# RX_DP.net
KiCad netlist of a schematic drawn in Altium Designer
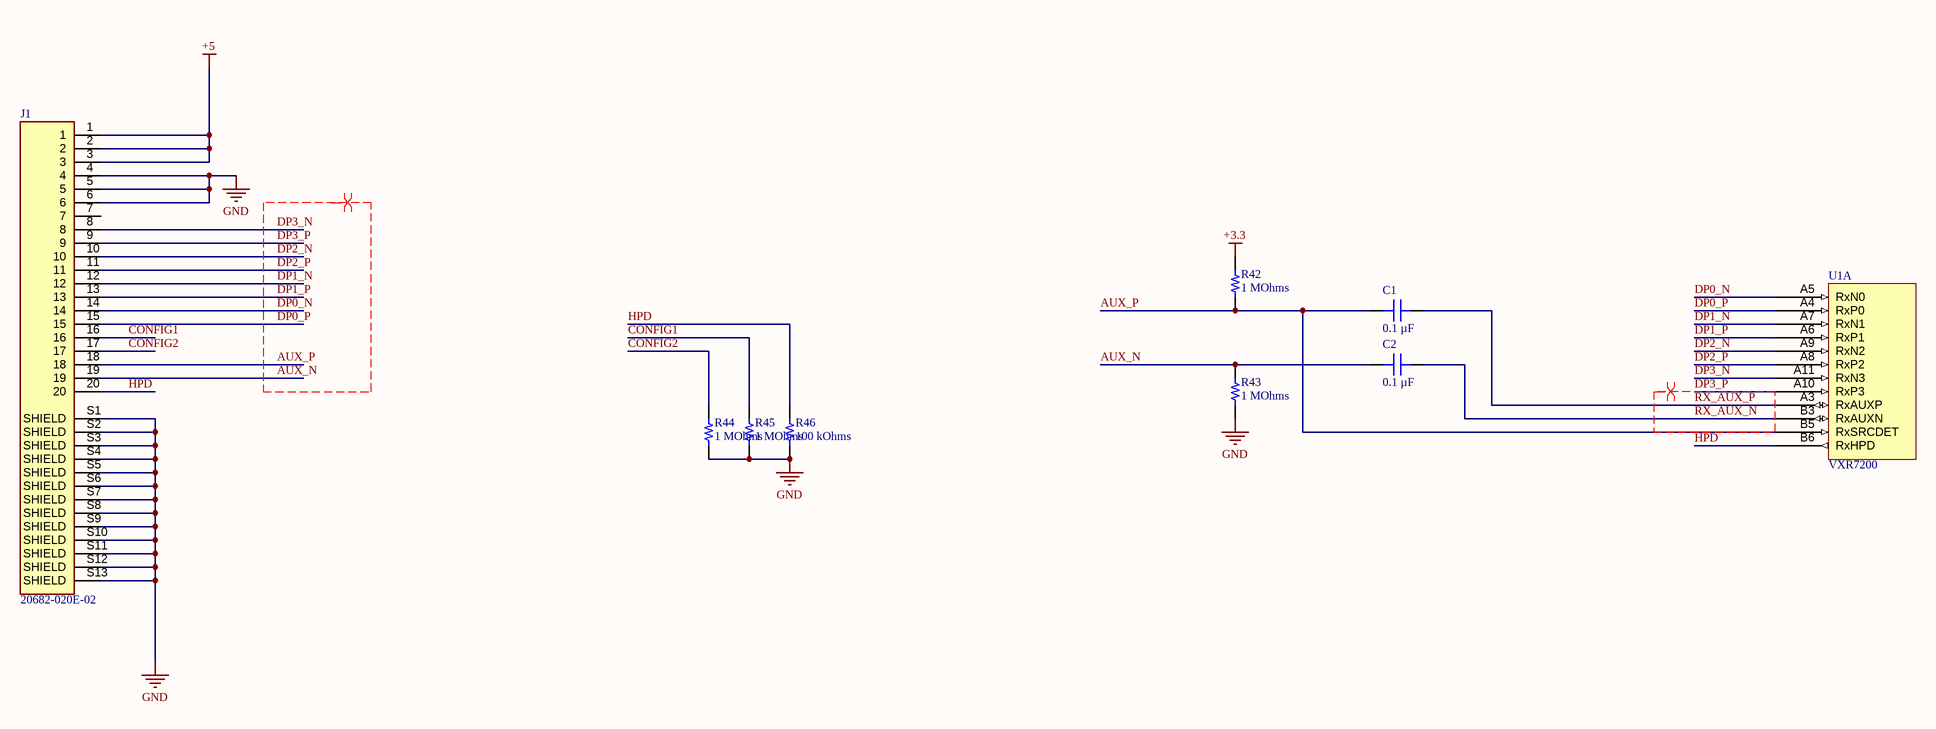
[diagram p0: RX_DP.SchDoc]

(export (version "E")
  (design (tool "Eeschema 10.0.6"))
  (components
    (comp (ref "C1")
      (value "0.1 µF")
      (footprint "CAP 0201_0603")
      (description "CAP CER 0.1UF 25V X5R 0201")
      (fields
        (field (name "PART NUMBER") "GRM033R61E104KE14D")
        (field (name "MANUFACTURER") "Murata Electronics")
      )
      (libsource (lib "Celestial Altium Library - altium_library") (part "Capacitor"))
    )
    (comp (ref "C2")
      (value "0.1 µF")
      (footprint "CAP 0201_0603")
      (description "CAP CER 0.1UF 25V X5R 0201")
      (fields
        (field (name "PART NUMBER") "GRM033R61E104KE14D")
        (field (name "MANUFACTURER") "Murata Electronics")
      )
      (libsource (lib "Celestial Altium Library - altium_library") (part "Capacitor"))
    )
    (comp (ref "J1")
      (value "20682-020E-02")
      (footprint "20682-020E-02:IPEX_20682-020E-02")
      (description "Cabline-CAII Rece. Ass'y")
      (fields (field (name "MF") "{'manufacturer': u'I-PEX'}"))
      (libsource (lib "20682-020E-02") (part "20682-020E-02"))
    )
    (comp (ref "R42")
      (value "1 MOhms")
      (footprint "RES 0201_0603")
      (description "RES SMD 1M OHM 1% 1/20W 0201")
      (fields (field (name "PART NUMBER") "CRCW02011M00FKED") (field (name "MANUFACTURER") "Vishay Dale"))
      (libsource (lib "Celestial Altium Library - altium_library") (part "Resistor"))
    )
    (comp (ref "R43")
      (value "1 MOhms")
      (footprint "RES 0201_0603")
      (description "RES SMD 1M OHM 1% 1/20W 0201")
      (fields (field (name "PART NUMBER") "CRCW02011M00FKED") (field (name "MANUFACTURER") "Vishay Dale"))
      (libsource (lib "Celestial Altium Library - altium_library") (part "Resistor"))
    )
    (comp (ref "R44")
      (value "1 MOhms")
      (footprint "RES 0201_0603")
      (description "RES SMD 1M OHM 1% 1/20W 0201")
      (fields (field (name "PART NUMBER") "CRCW02011M00FKED") (field (name "MANUFACTURER") "Vishay Dale"))
      (libsource (lib "Celestial Altium Library - altium_library") (part "Resistor"))
    )
    (comp (ref "R45")
      (value "1 MOhms")
      (footprint "RES 0201_0603")
      (description "RES SMD 1M OHM 1% 1/20W 0201")
      (fields (field (name "PART NUMBER") "CRCW02011M00FKED") (field (name "MANUFACTURER") "Vishay Dale"))
      (libsource (lib "Celestial Altium Library - altium_library") (part "Resistor"))
    )
    (comp (ref "R46")
      (value "100 kOhms")
      (footprint "RES 0201_0603")
      (description "RES 100K OHM 1% 1/20W 0201 SMD")
      (fields
        (field (name "PART NUMBER") "ERJ-U01F1003C")
        (field (name "MANUFACTURER") "Panasonic Electronic Components")
      )
      (libsource (lib "Celestial Altium Library - altium_library") (part "Resistor"))
    )
    (comp (ref "U1")
      (value "VXR7200")
      (footprint "BGA100P9X9-81A")
      (description "VXR7200 DP to MIPI-DSI bridge")
      (libsource (lib "SimulaVR") (part "VXR7200-Symbol-1"))
    )
  )
  (nets
    (net (code "1") (name "+3.3") (class "Default")
      (node (ref "R42") (pin "2") (pinfunction "2_2") (pintype "passive"))
    )
    (net (code "2") (name "+5") (class "Default")
      (node (ref "J1") (pin "1") (pinfunction "1_1") (pintype "passive"))
      (node (ref "J1") (pin "2") (pinfunction "2_2") (pintype "passive"))
      (node (ref "J1") (pin "3") (pinfunction "3_3") (pintype "passive"))
    )
    (net (code "3") (name "/AUX_N") (class "Default")
      (node (ref "C2") (pin "1") (pinfunction "1_1") (pintype "passive"))
      (node (ref "J1") (pin "19") (pinfunction "19_19") (pintype "passive"))
      (node (ref "R43") (pin "2") (pinfunction "2_2") (pintype "passive"))
    )
    (net (code "4") (name "/AUX_P") (class "Default")
      (node (ref "C1") (pin "1") (pinfunction "1_1") (pintype "passive"))
      (node (ref "J1") (pin "18") (pinfunction "18_18") (pintype "passive"))
      (node (ref "R42") (pin "1") (pinfunction "1_1") (pintype "passive"))
      (node (ref "U1") (pin "B5") (pinfunction "RxSRCDET_B5") (pintype "input"))
    )
    (net (code "5") (name "/CONFIG1") (class "Default")
      (node (ref "J1") (pin "16") (pinfunction "16_16") (pintype "passive"))
      (node (ref "R45") (pin "2") (pinfunction "2_2") (pintype "passive"))
    )
    (net (code "6") (name "/CONFIG2") (class "Default")
      (node (ref "J1") (pin "17") (pinfunction "17_17") (pintype "passive"))
      (node (ref "R44") (pin "2") (pinfunction "2_2") (pintype "passive"))
    )
    (net (code "7") (name "/DP0_N") (class "Default")
      (node (ref "J1") (pin "14") (pinfunction "14_14") (pintype "passive"))
      (node (ref "U1") (pin "A5") (pinfunction "RxN0_A5") (pintype "input"))
    )
    (net (code "8") (name "/DP0_P") (class "Default")
      (node (ref "J1") (pin "15") (pinfunction "15_15") (pintype "passive"))
      (node (ref "U1") (pin "A4") (pinfunction "RxP0_A4") (pintype "input"))
    )
    (net (code "9") (name "/DP1_N") (class "Default")
      (node (ref "J1") (pin "12") (pinfunction "12_12") (pintype "passive"))
      (node (ref "U1") (pin "A7") (pinfunction "RxN1_A7") (pintype "input"))
    )
    (net (code "10") (name "/DP1_P") (class "Default")
      (node (ref "J1") (pin "13") (pinfunction "13_13") (pintype "passive"))
      (node (ref "U1") (pin "A6") (pinfunction "RxP1_A6") (pintype "input"))
    )
    (net (code "11") (name "/DP2_N") (class "Default")
      (node (ref "J1") (pin "10") (pinfunction "10_10") (pintype "passive"))
      (node (ref "U1") (pin "A9") (pinfunction "RxN2_A9") (pintype "input"))
    )
    (net (code "12") (name "/DP2_P") (class "Default")
      (node (ref "J1") (pin "11") (pinfunction "11_11") (pintype "passive"))
      (node (ref "U1") (pin "A8") (pinfunction "RxP2_A8") (pintype "input"))
    )
    (net (code "13") (name "/DP3_N") (class "Default")
      (node (ref "J1") (pin "8") (pinfunction "8_8") (pintype "passive"))
      (node (ref "U1") (pin "A11") (pinfunction "RxN3_A11") (pintype "input"))
    )
    (net (code "14") (name "/DP3_P") (class "Default")
      (node (ref "J1") (pin "9") (pinfunction "9_9") (pintype "passive"))
      (node (ref "U1") (pin "A10") (pinfunction "RxP3_A10") (pintype "input"))
    )
    (net (code "15") (name "/HPD") (class "Default")
      (node (ref "J1") (pin "20") (pinfunction "20_20") (pintype "passive"))
      (node (ref "R46") (pin "2") (pinfunction "2_2") (pintype "passive"))
      (node (ref "U1") (pin "B6") (pinfunction "RxHPD_B6") (pintype "output"))
    )
    (net (code "16") (name "/RX_AUX_N") (class "Default")
      (node (ref "C2") (pin "2") (pinfunction "2_2") (pintype "passive"))
      (node (ref "U1") (pin "B3") (pinfunction "RxAUXN_B3") (pintype "bidirectional"))
    )
    (net (code "17") (name "/RX_AUX_P") (class "Default")
      (node (ref "C1") (pin "2") (pinfunction "2_2") (pintype "passive"))
      (node (ref "U1") (pin "A3") (pinfunction "RxAUXP_A3") (pintype "bidirectional"))
    )
    (net (code "18") (name "GND") (class "Default")
      (node (ref "J1") (pin "4") (pinfunction "4_4") (pintype "passive"))
      (node (ref "J1") (pin "5") (pinfunction "5_5") (pintype "passive"))
      (node (ref "J1") (pin "6") (pinfunction "6_6") (pintype "passive"))
      (node (ref "J1") (pin "S1") (pinfunction "SHIELD_S1") (pintype "passive"))
      (node (ref "J1") (pin "S10") (pinfunction "SHIELD_S10") (pintype "passive"))
      (node (ref "J1") (pin "S11") (pinfunction "SHIELD_S11") (pintype "passive"))
      (node (ref "J1") (pin "S12") (pinfunction "SHIELD_S12") (pintype "passive"))
      (node (ref "J1") (pin "S13") (pinfunction "SHIELD_S13") (pintype "passive"))
      (node (ref "J1") (pin "S2") (pinfunction "SHIELD_S2") (pintype "passive"))
      (node (ref "J1") (pin "S3") (pinfunction "SHIELD_S3") (pintype "passive"))
      (node (ref "J1") (pin "S4") (pinfunction "SHIELD_S4") (pintype "passive"))
      (node (ref "J1") (pin "S5") (pinfunction "SHIELD_S5") (pintype "passive"))
      (node (ref "J1") (pin "S6") (pinfunction "SHIELD_S6") (pintype "passive"))
      (node (ref "J1") (pin "S7") (pinfunction "SHIELD_S7") (pintype "passive"))
      (node (ref "J1") (pin "S8") (pinfunction "SHIELD_S8") (pintype "passive"))
      (node (ref "J1") (pin "S9") (pinfunction "SHIELD_S9") (pintype "passive"))
      (node (ref "R43") (pin "1") (pinfunction "1_1") (pintype "passive"))
      (node (ref "R44") (pin "1") (pinfunction "1_1") (pintype "passive"))
      (node (ref "R45") (pin "1") (pinfunction "1_1") (pintype "passive"))
      (node (ref "R46") (pin "1") (pinfunction "1_1") (pintype "passive"))
    )
    (net (code "19") (name "unconnected-(J1-Pad7)") (class "Default")
      (node (ref "J1") (pin "7") (pinfunction "7_7") (pintype "passive"))
    )
  )
)
